# MinimalDuino.net
KiCad netlist of a schematic drawn in EAGLE
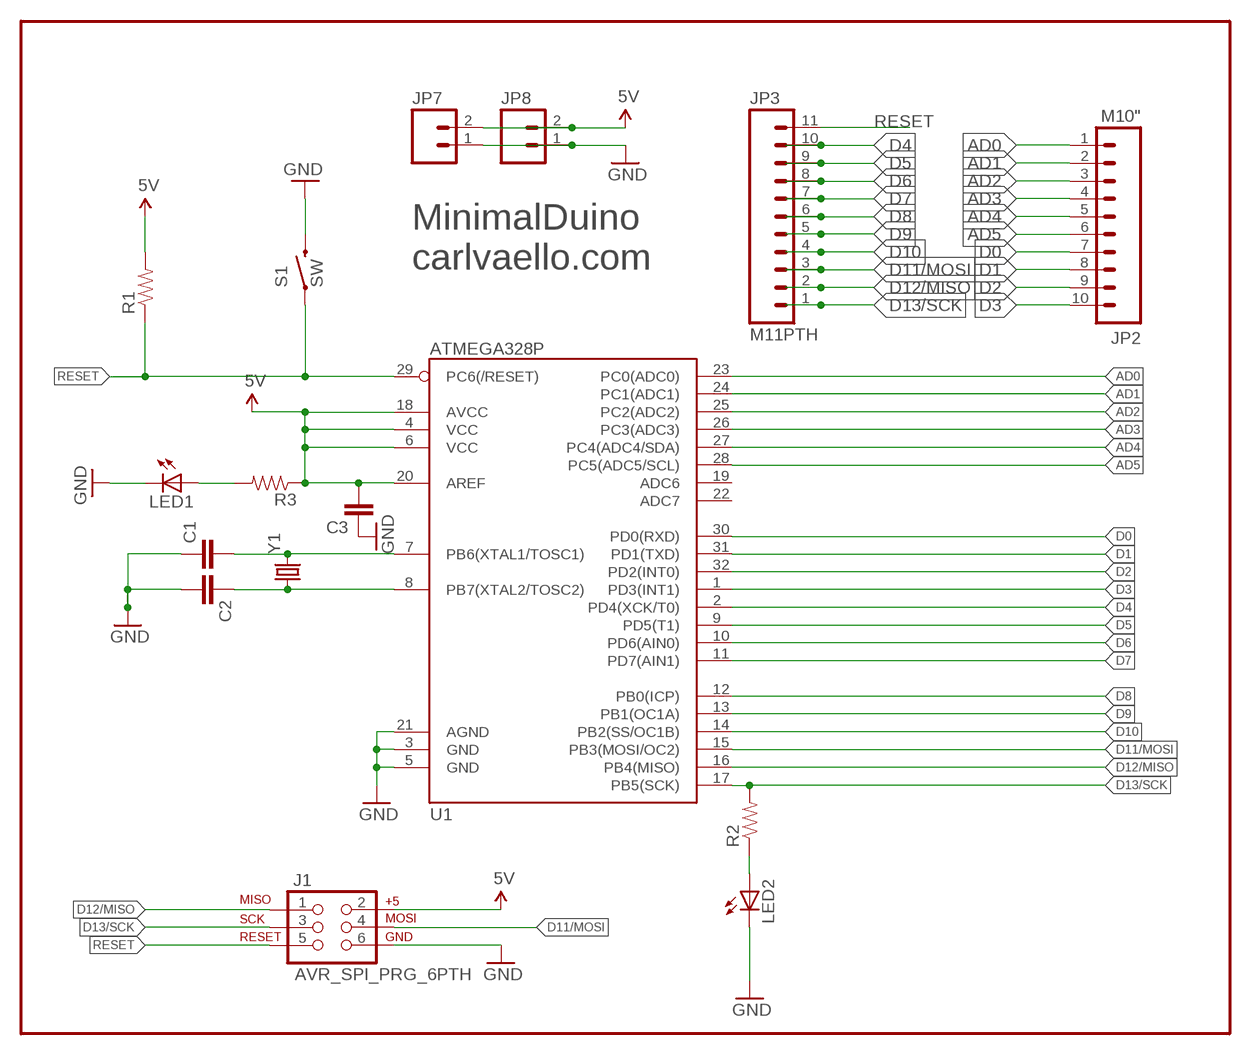
[diagram p0: schematic, sheet 1]

(export (version "E")
  (design (tool "Eeschema 10.0.6"))
  (components
    (comp (ref "C1")
      (value "CAP0805")
      (footprint "eagle-import:0805")
      (libsource (lib "eagle-import") (part "CAP0805"))
    )
    (comp (ref "C2")
      (value "CAP0805")
      (footprint "eagle-import:0805")
      (libsource (lib "eagle-import") (part "CAP0805"))
    )
    (comp (ref "C3")
      (value "CAP0805")
      (footprint "eagle-import:0805")
      (libsource (lib "eagle-import") (part "CAP0805"))
    )
    (comp (ref "J1")
      (value "AVR_SPI_PRG_6PTH")
      (footprint "eagle-import:2X3")
      (libsource (lib "eagle-import") (part "AVR_SPI_PRG_6PTH"))
    )
    (comp (ref "JP2")
      (value "M10\"")
      (footprint "eagle-import:1X10")
      (libsource (lib "eagle-import") (part "M10{dblquote}"))
    )
    (comp (ref "JP3")
      (value "M11PTH")
      (footprint "eagle-import:1X11")
      (libsource (lib "eagle-import") (part "M11PTH"))
    )
    (comp (ref "JP7")
      (value "M02PTH")
      (footprint "eagle-import:1X02")
      (libsource (lib "eagle-import") (part "M02PTH"))
    )
    (comp (ref "JP8")
      (value "M02PTH")
      (footprint "eagle-import:1X02")
      (libsource (lib "eagle-import") (part "M02PTH"))
    )
    (comp (ref "LED1")
      (value "LEDSML0805")
      (footprint "eagle-import:SML0805")
      (libsource (lib "eagle-import") (part "LEDSML0805"))
    )
    (comp (ref "LED2")
      (value "LEDSML0805")
      (footprint "eagle-import:SML0805")
      (libsource (lib "eagle-import") (part "LEDSML0805"))
    )
    (comp (ref "R1")
      (value "RESISTOR0805-RES")
      (footprint "eagle-import:0805")
      (libsource (lib "eagle-import") (part "RESISTOR0805-RES"))
    )
    (comp (ref "R2")
      (value "RESISTOR0805-RES")
      (footprint "eagle-import:0805")
      (libsource (lib "eagle-import") (part "RESISTOR0805-RES"))
    )
    (comp (ref "R3")
      (value "RESISTOR0805-RES")
      (footprint "eagle-import:0805")
      (libsource (lib "eagle-import") (part "RESISTOR0805-RES"))
    )
    (comp (ref "S1")
      (value "SW")
      (footprint "eagle-import:TACTILE-PTH-SIDEEZ")
      (libsource (lib "eagle-import") (part "SWITCH-MOMENTARY-2SIDE_EZ"))
    )
    (comp (ref "U1")
      (value "ATMEGA328P")
      (footprint "eagle-import:TQFP32-08")
      (libsource (lib "eagle-import") (part "ATMEGA328_SMT"))
    )
    (comp (ref "Y1")
      (value "CRYSTALHC49US")
      (footprint "eagle-import:HC49US")
      (libsource (lib "eagle-import") (part "CRYSTALHC49US"))
    )
  )
  (nets
    (net (code "1") (name "5V") (class "Default")
      (node (ref "C3") (pin "2") (pinfunction "2_2") (pintype "passive"))
      (node (ref "J1") (pin "2") (pinfunction "2_2") (pintype "passive"))
      (node (ref "JP7") (pin "2") (pinfunction "2_2") (pintype "passive"))
      (node (ref "JP8") (pin "2") (pinfunction "2_2") (pintype "passive"))
      (node (ref "R1") (pin "2") (pinfunction "2_2") (pintype "passive"))
      (node (ref "R3") (pin "1") (pinfunction "1_1") (pintype "passive"))
      (node (ref "U1") (pin "18") (pinfunction "AVCC_18") (pintype "bidirectional"))
      (node (ref "U1") (pin "20") (pinfunction "AREF_20") (pintype "bidirectional"))
      (node (ref "U1") (pin "4") (pinfunction "VCC_4") (pintype "bidirectional"))
      (node (ref "U1") (pin "6") (pinfunction "VCC_6") (pintype "bidirectional"))
    )
    (net (code "2") (name "AD0") (class "Default")
      (node (ref "JP2") (pin "1") (pinfunction "1_1") (pintype "passive"))
      (node (ref "U1") (pin "23") (pinfunction "PC0(ADC0)_23") (pintype "bidirectional"))
    )
    (net (code "3") (name "AD1") (class "Default")
      (node (ref "JP2") (pin "2") (pinfunction "2_2") (pintype "passive"))
      (node (ref "U1") (pin "24") (pinfunction "PC1(ADC1)_24") (pintype "bidirectional"))
    )
    (net (code "4") (name "AD2") (class "Default")
      (node (ref "JP2") (pin "3") (pinfunction "3_3") (pintype "passive"))
      (node (ref "U1") (pin "25") (pinfunction "PC2(ADC2)_25") (pintype "bidirectional"))
    )
    (net (code "5") (name "AD3") (class "Default")
      (node (ref "JP2") (pin "4") (pinfunction "4_4") (pintype "passive"))
      (node (ref "U1") (pin "26") (pinfunction "PC3(ADC3)_26") (pintype "bidirectional"))
    )
    (net (code "6") (name "AD4") (class "Default")
      (node (ref "JP2") (pin "5") (pinfunction "5_5") (pintype "passive"))
      (node (ref "U1") (pin "27") (pinfunction "PC4(ADC4/SDA)_27") (pintype "bidirectional"))
    )
    (net (code "7") (name "AD5") (class "Default")
      (node (ref "JP2") (pin "6") (pinfunction "6_6") (pintype "passive"))
      (node (ref "U1") (pin "28") (pinfunction "PC5(ADC5/SCL)_28") (pintype "bidirectional"))
    )
    (net (code "8") (name "D0") (class "Default")
      (node (ref "JP2") (pin "7") (pinfunction "7_7") (pintype "passive"))
      (node (ref "U1") (pin "30") (pinfunction "PD0(RXD)_30") (pintype "bidirectional"))
    )
    (net (code "9") (name "D1") (class "Default")
      (node (ref "JP2") (pin "8") (pinfunction "8_8") (pintype "passive"))
      (node (ref "U1") (pin "31") (pinfunction "PD1(TXD)_31") (pintype "bidirectional"))
    )
    (net (code "10") (name "D2") (class "Default")
      (node (ref "JP2") (pin "9") (pinfunction "9_9") (pintype "passive"))
      (node (ref "U1") (pin "32") (pinfunction "PD2(INT0)_32") (pintype "bidirectional"))
    )
    (net (code "11") (name "D3") (class "Default")
      (node (ref "JP2") (pin "10") (pinfunction "10_10") (pintype "passive"))
      (node (ref "U1") (pin "1") (pinfunction "PD3(INT1)_1") (pintype "bidirectional"))
    )
    (net (code "12") (name "D4") (class "Default")
      (node (ref "JP3") (pin "10") (pinfunction "10_10") (pintype "passive"))
      (node (ref "U1") (pin "2") (pinfunction "PD4(XCK/T0)_2") (pintype "bidirectional"))
    )
    (net (code "13") (name "D5") (class "Default")
      (node (ref "JP3") (pin "9") (pinfunction "9_9") (pintype "passive"))
      (node (ref "U1") (pin "9") (pinfunction "PD5(T1)_9") (pintype "bidirectional"))
    )
    (net (code "14") (name "D6") (class "Default")
      (node (ref "JP3") (pin "8") (pinfunction "8_8") (pintype "passive"))
      (node (ref "U1") (pin "10") (pinfunction "PD6(AIN0)_10") (pintype "bidirectional"))
    )
    (net (code "15") (name "D7") (class "Default")
      (node (ref "JP3") (pin "7") (pinfunction "7_7") (pintype "passive"))
      (node (ref "U1") (pin "11") (pinfunction "PD7(AIN1)_11") (pintype "bidirectional"))
    )
    (net (code "16") (name "D8") (class "Default")
      (node (ref "JP3") (pin "6") (pinfunction "6_6") (pintype "passive"))
      (node (ref "U1") (pin "12") (pinfunction "PB0(ICP)_12") (pintype "bidirectional"))
    )
    (net (code "17") (name "D9") (class "Default")
      (node (ref "JP3") (pin "5") (pinfunction "5_5") (pintype "passive"))
      (node (ref "U1") (pin "13") (pinfunction "PB1(OC1A)_13") (pintype "bidirectional"))
    )
    (net (code "18") (name "D10") (class "Default")
      (node (ref "JP3") (pin "4") (pinfunction "4_4") (pintype "passive"))
      (node (ref "U1") (pin "14") (pinfunction "PB2(SS/OC1B)_14") (pintype "bidirectional"))
    )
    (net (code "19") (name "D11{slash}MOSI") (class "Default")
      (node (ref "J1") (pin "4") (pinfunction "4_4") (pintype "passive"))
      (node (ref "JP3") (pin "3") (pinfunction "3_3") (pintype "passive"))
      (node (ref "U1") (pin "15") (pinfunction "PB3(MOSI/OC2)_15") (pintype "bidirectional"))
    )
    (net (code "20") (name "D12{slash}MISO") (class "Default")
      (node (ref "J1") (pin "1") (pinfunction "1_1") (pintype "passive"))
      (node (ref "JP3") (pin "2") (pinfunction "2_2") (pintype "passive"))
      (node (ref "U1") (pin "16") (pinfunction "PB4(MISO)_16") (pintype "bidirectional"))
    )
    (net (code "21") (name "D13{slash}SCK") (class "Default")
      (node (ref "J1") (pin "3") (pinfunction "3_3") (pintype "passive"))
      (node (ref "JP3") (pin "1") (pinfunction "1_1") (pintype "passive"))
      (node (ref "R2") (pin "2") (pinfunction "2_2") (pintype "passive"))
      (node (ref "U1") (pin "17") (pinfunction "PB5(SCK)_17") (pintype "bidirectional"))
    )
    (net (code "22") (name "GND") (class "Default")
      (node (ref "C1") (pin "1") (pinfunction "1_1") (pintype "passive"))
      (node (ref "C2") (pin "2") (pinfunction "2_2") (pintype "passive"))
      (node (ref "C3") (pin "1") (pinfunction "1_1") (pintype "passive"))
      (node (ref "J1") (pin "6") (pinfunction "6_6") (pintype "passive"))
      (node (ref "JP7") (pin "1") (pinfunction "1_1") (pintype "passive"))
      (node (ref "JP8") (pin "1") (pinfunction "1_1") (pintype "passive"))
      (node (ref "LED1") (pin "C") (pinfunction "C_C") (pintype "passive"))
      (node (ref "LED2") (pin "C") (pinfunction "C_C") (pintype "passive"))
      (node (ref "S1") (pin "2") (pinfunction "2_2") (pintype "passive"))
      (node (ref "U1") (pin "21") (pinfunction "AGND_21") (pintype "bidirectional"))
      (node (ref "U1") (pin "3") (pinfunction "GND_3") (pintype "bidirectional"))
      (node (ref "U1") (pin "5") (pinfunction "GND_5") (pintype "bidirectional"))
    )
    (net (code "23") (name "Net-(LED1-PadA)") (class "Default")
      (node (ref "LED1") (pin "A") (pinfunction "A_A") (pintype "passive"))
      (node (ref "R3") (pin "2") (pinfunction "2_2") (pintype "passive"))
    )
    (net (code "24") (name "Net-(LED2-PadA)") (class "Default")
      (node (ref "LED2") (pin "A") (pinfunction "A_A") (pintype "passive"))
      (node (ref "R2") (pin "1") (pinfunction "1_1") (pintype "passive"))
    )
    (net (code "25") (name "Net-(U1-PB6(XTAL1{slash}TOSC1))") (class "Default")
      (node (ref "C1") (pin "2") (pinfunction "2_2") (pintype "passive"))
      (node (ref "U1") (pin "7") (pinfunction "PB6(XTAL1/TOSC1)_7") (pintype "bidirectional"))
      (node (ref "Y1") (pin "2") (pinfunction "2_2") (pintype "passive"))
    )
    (net (code "26") (name "Net-(U1-PB7(XTAL2{slash}TOSC2))") (class "Default")
      (node (ref "C2") (pin "1") (pinfunction "1_1") (pintype "passive"))
      (node (ref "U1") (pin "8") (pinfunction "PB7(XTAL2/TOSC2)_8") (pintype "bidirectional"))
      (node (ref "Y1") (pin "1") (pinfunction "1_1") (pintype "passive"))
    )
    (net (code "27") (name "RESET") (class "Default")
      (node (ref "J1") (pin "5") (pinfunction "5_5") (pintype "passive"))
      (node (ref "JP3") (pin "11") (pinfunction "11_11") (pintype "passive"))
      (node (ref "R1") (pin "1") (pinfunction "1_1") (pintype "passive"))
      (node (ref "S1") (pin "1") (pinfunction "1_1") (pintype "passive"))
      (node (ref "U1") (pin "29") (pinfunction "PC6(/RESET)_29") (pintype "bidirectional"))
    )
    (net (code "28") (name "unconnected-(U1-ADC6-Pad19)") (class "Default")
      (node (ref "U1") (pin "19") (pinfunction "ADC6_19") (pintype "bidirectional"))
    )
    (net (code "29") (name "unconnected-(U1-ADC7-Pad22)") (class "Default")
      (node (ref "U1") (pin "22") (pinfunction "ADC7_22") (pintype "bidirectional"))
    )
  )
)
